# PLCArduinoV1.net
KiCad netlist of a schematic drawn in EAGLE
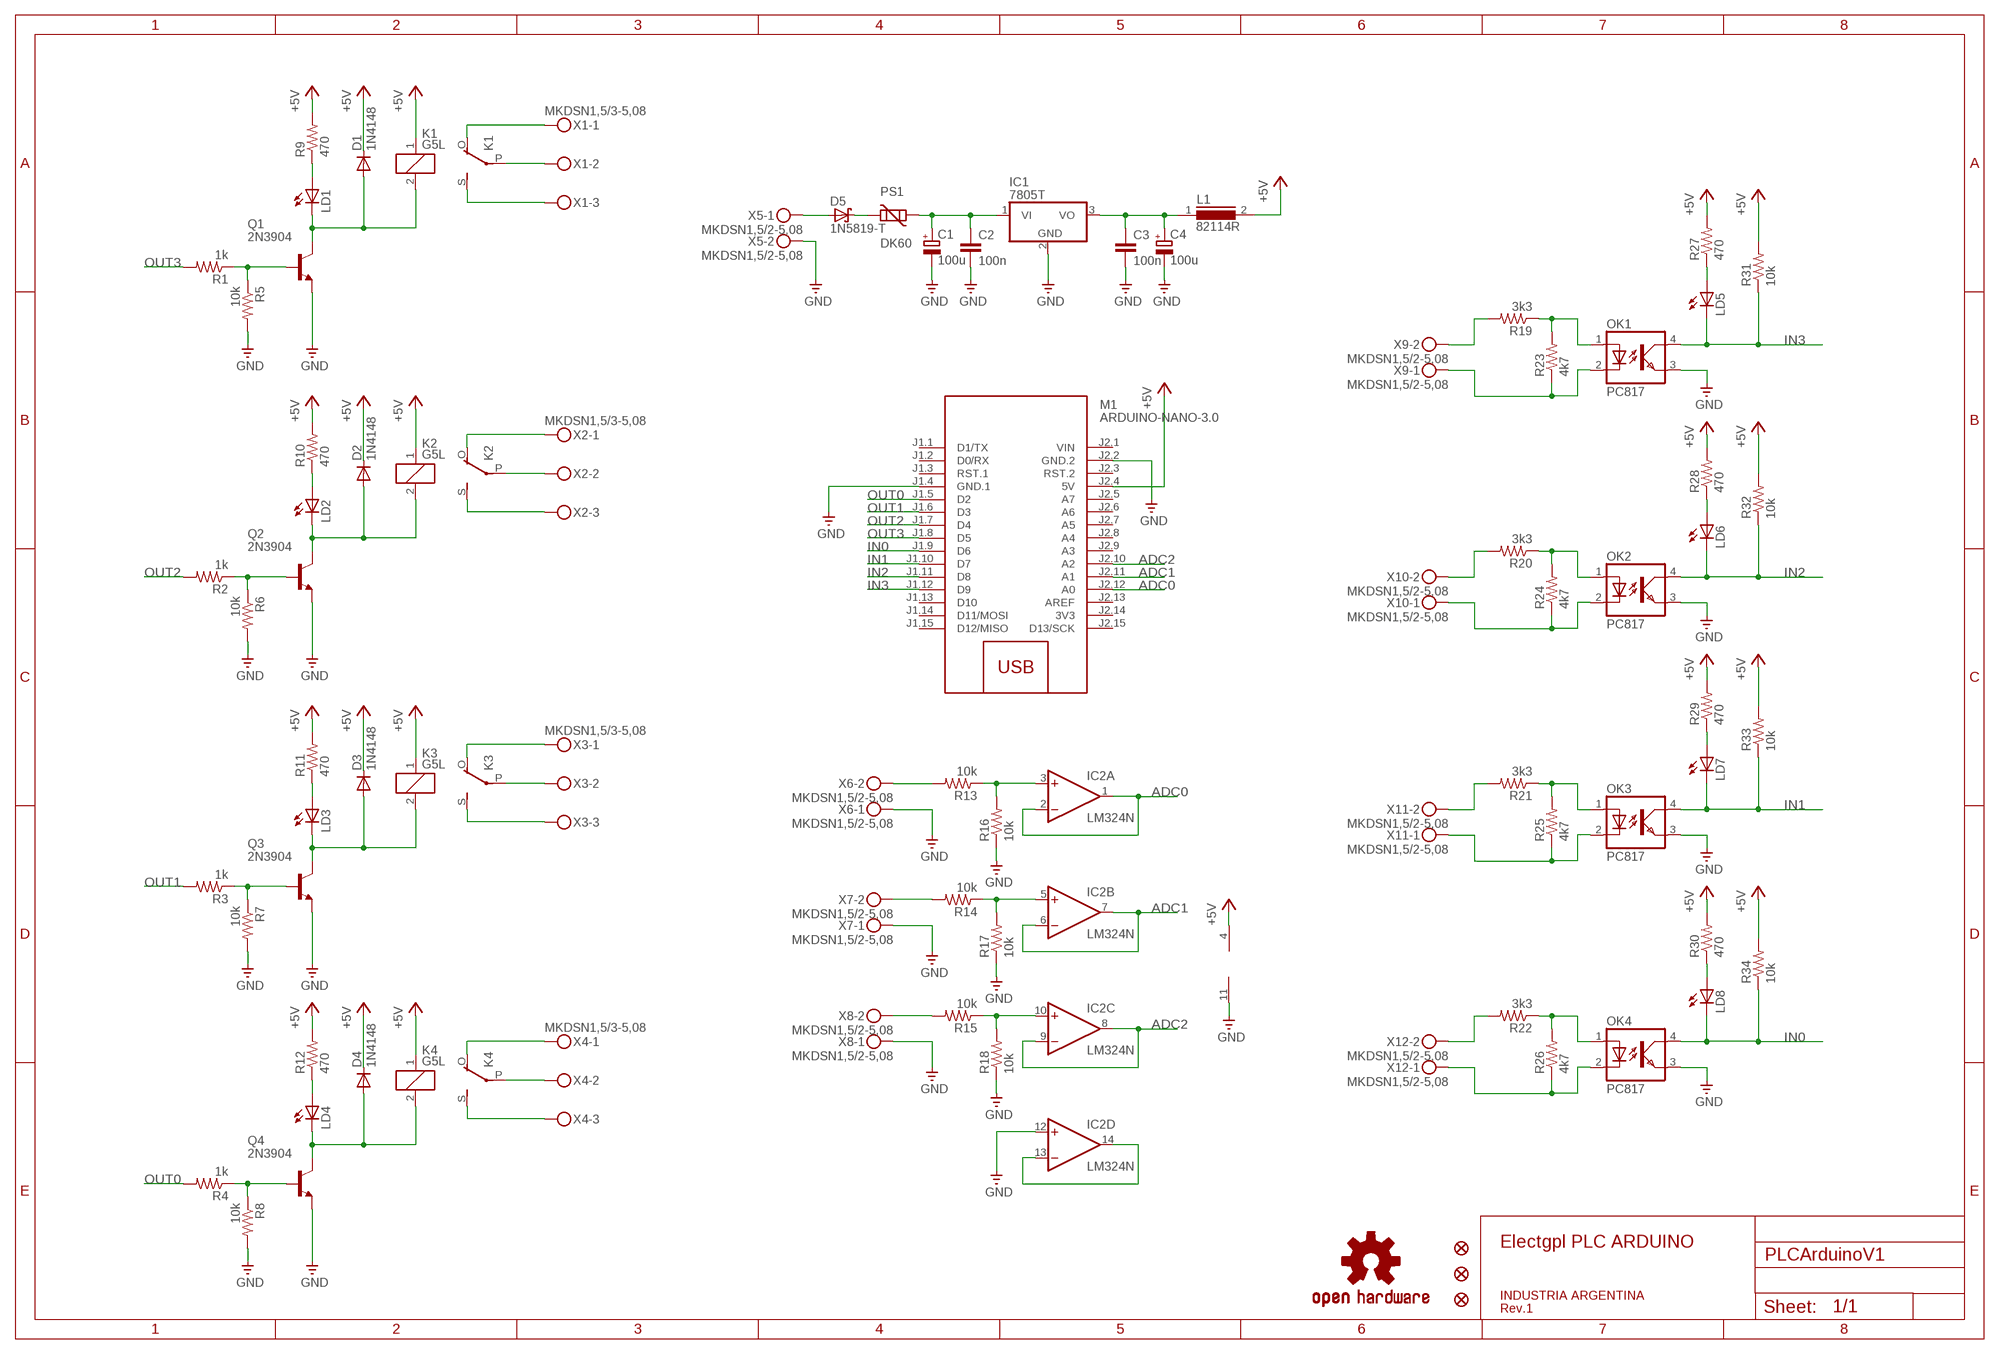
[diagram p0: schematic, sheet 1]

(export (version "E")
  (design (tool "Eeschema 10.0.6"))
  (components
    (comp (ref "C1")
      (value "100u")
      (footprint "eagle-import:E3,5-8")
      (libsource (lib "eagle-import") (part "CPOL-EUE3.5-8"))
    )
    (comp (ref "C2")
      (value "100n")
      (footprint "eagle-import:C050-024X044")
      (libsource (lib "eagle-import") (part "C-EU050-024X044"))
    )
    (comp (ref "C3")
      (value "100n")
      (footprint "eagle-import:C050-024X044")
      (libsource (lib "eagle-import") (part "C-EU050-024X044"))
    )
    (comp (ref "C4")
      (value "100u")
      (footprint "eagle-import:E3,5-8")
      (libsource (lib "eagle-import") (part "CPOL-EUE3.5-8"))
    )
    (comp (ref "D1")
      (value "1N4148")
      (footprint "eagle-import:DO35-10")
      (libsource (lib "eagle-import") (part "1N4148"))
    )
    (comp (ref "D2")
      (value "1N4148")
      (footprint "eagle-import:DO35-10")
      (libsource (lib "eagle-import") (part "1N4148"))
    )
    (comp (ref "D3")
      (value "1N4148")
      (footprint "eagle-import:DO35-10")
      (libsource (lib "eagle-import") (part "1N4148"))
    )
    (comp (ref "D4")
      (value "1N4148")
      (footprint "eagle-import:DO35-10")
      (libsource (lib "eagle-import") (part "1N4148"))
    )
    (comp (ref "D5")
      (value "1N5819-T")
      (footprint "eagle-import:DO41-7.6")
      (libsource (lib "eagle-import") (part "1N5819-T"))
    )
    (comp (ref "IC1")
      (value "7805T")
      (footprint "eagle-import:TO220H")
      (libsource (lib "eagle-import") (part "78T05"))
    )
    (comp (ref "IC2")
      (value "LM324N")
      (footprint "eagle-import:DIL14")
      (libsource (lib "eagle-import") (part "LM324N"))
    )
    (comp (ref "JP1")
      (value "FIDUCIAL1X2.5")
      (footprint "eagle-import:FIDUCIAL-1X2.5")
      (libsource (lib "eagle-import") (part "FIDUCIAL1X2.5"))
    )
    (comp (ref "JP2")
      (value "FIDUCIAL1X2.5")
      (footprint "eagle-import:FIDUCIAL-1X2.5")
      (libsource (lib "eagle-import") (part "FIDUCIAL1X2.5"))
    )
    (comp (ref "JP3")
      (value "FIDUCIAL1X2.5")
      (footprint "eagle-import:FIDUCIAL-1X2.5")
      (libsource (lib "eagle-import") (part "FIDUCIAL1X2.5"))
    )
    (comp (ref "K1")
      (value "G5L")
      (footprint "eagle-import:G5LE")
      (libsource (lib "eagle-import") (part "G5L"))
    )
    (comp (ref "K2")
      (value "G5L")
      (footprint "eagle-import:G5LE")
      (libsource (lib "eagle-import") (part "G5L"))
    )
    (comp (ref "K3")
      (value "G5L")
      (footprint "eagle-import:G5LE")
      (libsource (lib "eagle-import") (part "G5L"))
    )
    (comp (ref "K4")
      (value "G5L")
      (footprint "eagle-import:G5LE")
      (libsource (lib "eagle-import") (part "G5L"))
    )
    (comp (ref "L1")
      (value "82114R")
      (footprint "eagle-import:82114R")
      (libsource (lib "eagle-import") (part "82114R"))
    )
    (comp (ref "LD1")
      (value "LED3MM")
      (footprint "eagle-import:LED3MM")
      (libsource (lib "eagle-import") (part "LED3MM"))
    )
    (comp (ref "LD2")
      (value "LED3MM")
      (footprint "eagle-import:LED3MM")
      (libsource (lib "eagle-import") (part "LED3MM"))
    )
    (comp (ref "LD3")
      (value "LED3MM")
      (footprint "eagle-import:LED3MM")
      (libsource (lib "eagle-import") (part "LED3MM"))
    )
    (comp (ref "LD4")
      (value "LED3MM")
      (footprint "eagle-import:LED3MM")
      (libsource (lib "eagle-import") (part "LED3MM"))
    )
    (comp (ref "LD5")
      (value "LED3MM")
      (footprint "eagle-import:LED3MM")
      (libsource (lib "eagle-import") (part "LED3MM"))
    )
    (comp (ref "LD6")
      (value "LED3MM")
      (footprint "eagle-import:LED3MM")
      (libsource (lib "eagle-import") (part "LED3MM"))
    )
    (comp (ref "LD7")
      (value "LED3MM")
      (footprint "eagle-import:LED3MM")
      (libsource (lib "eagle-import") (part "LED3MM"))
    )
    (comp (ref "LD8")
      (value "LED3MM")
      (footprint "eagle-import:LED3MM")
      (libsource (lib "eagle-import") (part "LED3MM"))
    )
    (comp (ref "M1")
      (value "ARDUINO-NANO-3.0")
      (footprint "eagle-import:ARDUINO-NANO-3.0")
      (libsource (lib "eagle-import") (part "ARDUINO-NANO-3.0"))
    )
    (comp (ref "OK1")
      (value "PC817")
      (footprint "eagle-import:DIL04")
      (libsource (lib "eagle-import") (part "PC817"))
    )
    (comp (ref "OK2")
      (value "PC817")
      (footprint "eagle-import:DIL04")
      (libsource (lib "eagle-import") (part "PC817"))
    )
    (comp (ref "OK3")
      (value "PC817")
      (footprint "eagle-import:DIL04")
      (libsource (lib "eagle-import") (part "PC817"))
    )
    (comp (ref "OK4")
      (value "PC817")
      (footprint "eagle-import:DIL04")
      (libsource (lib "eagle-import") (part "PC817"))
    )
    (comp (ref "PS1")
      (value "DK60")
      (footprint "eagle-import:SO5K11")
      (libsource (lib "eagle-import") (part "POLYSWITCH5MM"))
    )
    (comp (ref "Q1")
      (value "2N3904")
      (footprint "eagle-import:TO92")
      (libsource (lib "eagle-import") (part "2N3904"))
    )
    (comp (ref "Q2")
      (value "2N3904")
      (footprint "eagle-import:TO92")
      (libsource (lib "eagle-import") (part "2N3904"))
    )
    (comp (ref "Q3")
      (value "2N3904")
      (footprint "eagle-import:TO92")
      (libsource (lib "eagle-import") (part "2N3904"))
    )
    (comp (ref "Q4")
      (value "2N3904")
      (footprint "eagle-import:TO92")
      (libsource (lib "eagle-import") (part "2N3904"))
    )
    (comp (ref "R1")
      (value "1k")
      (footprint "eagle-import:0204_5")
      (libsource (lib "eagle-import") (part "R-US_0204/5"))
    )
    (comp (ref "R2")
      (value "1k")
      (footprint "eagle-import:0204_5")
      (libsource (lib "eagle-import") (part "R-US_0204/5"))
    )
    (comp (ref "R3")
      (value "1k")
      (footprint "eagle-import:0204_5")
      (libsource (lib "eagle-import") (part "R-US_0204/5"))
    )
    (comp (ref "R4")
      (value "1k")
      (footprint "eagle-import:0204_5")
      (libsource (lib "eagle-import") (part "R-US_0204/5"))
    )
    (comp (ref "R5")
      (value "10k")
      (footprint "eagle-import:0204_5")
      (libsource (lib "eagle-import") (part "R-US_0204/5"))
    )
    (comp (ref "R6")
      (value "10k")
      (footprint "eagle-import:0204_5")
      (libsource (lib "eagle-import") (part "R-US_0204/5"))
    )
    (comp (ref "R7")
      (value "10k")
      (footprint "eagle-import:0204_5")
      (libsource (lib "eagle-import") (part "R-US_0204/5"))
    )
    (comp (ref "R8")
      (value "10k")
      (footprint "eagle-import:0204_5")
      (libsource (lib "eagle-import") (part "R-US_0204/5"))
    )
    (comp (ref "R9")
      (value "470")
      (footprint "eagle-import:0204_5")
      (libsource (lib "eagle-import") (part "R-US_0204/5"))
    )
    (comp (ref "R10")
      (value "470")
      (footprint "eagle-import:0204_5")
      (libsource (lib "eagle-import") (part "R-US_0204/5"))
    )
    (comp (ref "R11")
      (value "470")
      (footprint "eagle-import:0204_5")
      (libsource (lib "eagle-import") (part "R-US_0204/5"))
    )
    (comp (ref "R12")
      (value "470")
      (footprint "eagle-import:0204_5")
      (libsource (lib "eagle-import") (part "R-US_0204/5"))
    )
    (comp (ref "R13")
      (value "10k")
      (footprint "eagle-import:0204_5")
      (libsource (lib "eagle-import") (part "R-US_0204/5"))
    )
    (comp (ref "R14")
      (value "10k")
      (footprint "eagle-import:0204_5")
      (libsource (lib "eagle-import") (part "R-US_0204/5"))
    )
    (comp (ref "R15")
      (value "10k")
      (footprint "eagle-import:0204_5")
      (libsource (lib "eagle-import") (part "R-US_0204/5"))
    )
    (comp (ref "R16")
      (value "10k")
      (footprint "eagle-import:0204_5")
      (libsource (lib "eagle-import") (part "R-US_0204/5"))
    )
    (comp (ref "R17")
      (value "10k")
      (footprint "eagle-import:0204_5")
      (libsource (lib "eagle-import") (part "R-US_0204/5"))
    )
    (comp (ref "R18")
      (value "10k")
      (footprint "eagle-import:0204_5")
      (libsource (lib "eagle-import") (part "R-US_0204/5"))
    )
    (comp (ref "R19")
      (value "3k3")
      (footprint "eagle-import:0204_5")
      (libsource (lib "eagle-import") (part "R-US_0204/5"))
    )
    (comp (ref "R20")
      (value "3k3")
      (footprint "eagle-import:0204_5")
      (libsource (lib "eagle-import") (part "R-US_0204/5"))
    )
    (comp (ref "R21")
      (value "3k3")
      (footprint "eagle-import:0204_5")
      (libsource (lib "eagle-import") (part "R-US_0204/5"))
    )
    (comp (ref "R22")
      (value "3k3")
      (footprint "eagle-import:0204_5")
      (libsource (lib "eagle-import") (part "R-US_0204/5"))
    )
    (comp (ref "R23")
      (value "4k7")
      (footprint "eagle-import:0204_5")
      (libsource (lib "eagle-import") (part "R-US_0204/5"))
    )
    (comp (ref "R24")
      (value "4k7")
      (footprint "eagle-import:0204_5")
      (libsource (lib "eagle-import") (part "R-US_0204/5"))
    )
    (comp (ref "R25")
      (value "4k7")
      (footprint "eagle-import:0204_5")
      (libsource (lib "eagle-import") (part "R-US_0204/5"))
    )
    (comp (ref "R26")
      (value "4k7")
      (footprint "eagle-import:0204_5")
      (libsource (lib "eagle-import") (part "R-US_0204/5"))
    )
    (comp (ref "R27")
      (value "470")
      (footprint "eagle-import:0204_5")
      (libsource (lib "eagle-import") (part "R-US_0204/5"))
    )
    (comp (ref "R28")
      (value "470")
      (footprint "eagle-import:0204_5")
      (libsource (lib "eagle-import") (part "R-US_0204/5"))
    )
    (comp (ref "R29")
      (value "470")
      (footprint "eagle-import:0204_5")
      (libsource (lib "eagle-import") (part "R-US_0204/5"))
    )
    (comp (ref "R30")
      (value "470")
      (footprint "eagle-import:0204_5")
      (libsource (lib "eagle-import") (part "R-US_0204/5"))
    )
    (comp (ref "R31")
      (value "10k")
      (footprint "eagle-import:0204_5")
      (libsource (lib "eagle-import") (part "R-US_0204/5"))
    )
    (comp (ref "R32")
      (value "10k")
      (footprint "eagle-import:0204_5")
      (libsource (lib "eagle-import") (part "R-US_0204/5"))
    )
    (comp (ref "R33")
      (value "10k")
      (footprint "eagle-import:0204_5")
      (libsource (lib "eagle-import") (part "R-US_0204/5"))
    )
    (comp (ref "R34")
      (value "10k")
      (footprint "eagle-import:0204_5")
      (libsource (lib "eagle-import") (part "R-US_0204/5"))
    )
    (comp (ref "U1")
      (value "OSHW-LOGOM")
      (footprint "eagle-import:OSHW-LOGO-M")
      (libsource (lib "eagle-import") (part "OSHW-LOGOM"))
    )
    (comp (ref "X1")
      (value "MKDSN1,5/3-5,08")
      (footprint "eagle-import:MKDSN1,5_3-5,08")
      (libsource (lib "eagle-import") (part "MKDSN1,5/3-5,08"))
    )
    (comp (ref "X2")
      (value "MKDSN1,5/3-5,08")
      (footprint "eagle-import:MKDSN1,5_3-5,08")
      (libsource (lib "eagle-import") (part "MKDSN1,5/3-5,08"))
    )
    (comp (ref "X3")
      (value "MKDSN1,5/3-5,08")
      (footprint "eagle-import:MKDSN1,5_3-5,08")
      (libsource (lib "eagle-import") (part "MKDSN1,5/3-5,08"))
    )
    (comp (ref "X4")
      (value "MKDSN1,5/3-5,08")
      (footprint "eagle-import:MKDSN1,5_3-5,08")
      (libsource (lib "eagle-import") (part "MKDSN1,5/3-5,08"))
    )
    (comp (ref "X5")
      (value "MKDSN1,5/2-5,08")
      (footprint "eagle-import:MKDSN1,5_2-5,08")
      (libsource (lib "eagle-import") (part "MKDSN1,5/2-5,08"))
    )
    (comp (ref "X6")
      (value "MKDSN1,5/2-5,08")
      (footprint "eagle-import:MKDSN1,5_2-5,08")
      (libsource (lib "eagle-import") (part "MKDSN1,5/2-5,08"))
    )
    (comp (ref "X7")
      (value "MKDSN1,5/2-5,08")
      (footprint "eagle-import:MKDSN1,5_2-5,08")
      (libsource (lib "eagle-import") (part "MKDSN1,5/2-5,08"))
    )
    (comp (ref "X8")
      (value "MKDSN1,5/2-5,08")
      (footprint "eagle-import:MKDSN1,5_2-5,08")
      (libsource (lib "eagle-import") (part "MKDSN1,5/2-5,08"))
    )
    (comp (ref "X9")
      (value "MKDSN1,5/2-5,08")
      (footprint "eagle-import:MKDSN1,5_2-5,08")
      (libsource (lib "eagle-import") (part "MKDSN1,5/2-5,08"))
    )
    (comp (ref "X10")
      (value "MKDSN1,5/2-5,08")
      (footprint "eagle-import:MKDSN1,5_2-5,08")
      (libsource (lib "eagle-import") (part "MKDSN1,5/2-5,08"))
    )
    (comp (ref "X11")
      (value "MKDSN1,5/2-5,08")
      (footprint "eagle-import:MKDSN1,5_2-5,08")
      (libsource (lib "eagle-import") (part "MKDSN1,5/2-5,08"))
    )
    (comp (ref "X12")
      (value "MKDSN1,5/2-5,08")
      (footprint "eagle-import:MKDSN1,5_2-5,08")
      (libsource (lib "eagle-import") (part "MKDSN1,5/2-5,08"))
    )
  )
  (nets
    (net (code "1") (name "+5V") (class "Default")
      (node (ref "D1") (pin "C") (pinfunction "C_C") (pintype "passive"))
      (node (ref "D2") (pin "C") (pinfunction "C_C") (pintype "passive"))
      (node (ref "D3") (pin "C") (pinfunction "C_C") (pintype "passive"))
      (node (ref "D4") (pin "C") (pinfunction "C_C") (pintype "passive"))
      (node (ref "IC2") (pin "4") (pinfunction "V+_4") (pintype "power_in"))
      (node (ref "K1") (pin "1") (pinfunction "1_1") (pintype "passive"))
      (node (ref "K2") (pin "1") (pinfunction "1_1") (pintype "passive"))
      (node (ref "K3") (pin "1") (pinfunction "1_1") (pintype "passive"))
      (node (ref "K4") (pin "1") (pinfunction "1_1") (pintype "passive"))
      (node (ref "L1") (pin "2") (pinfunction "2_2") (pintype "passive"))
      (node (ref "M1") (pin "J2.4") (pinfunction "5V_J2.4") (pintype "power_in"))
      (node (ref "R10") (pin "2") (pinfunction "2_2") (pintype "passive"))
      (node (ref "R11") (pin "2") (pinfunction "2_2") (pintype "passive"))
      (node (ref "R12") (pin "2") (pinfunction "2_2") (pintype "passive"))
      (node (ref "R27") (pin "2") (pinfunction "2_2") (pintype "passive"))
      (node (ref "R28") (pin "2") (pinfunction "2_2") (pintype "passive"))
      (node (ref "R29") (pin "2") (pinfunction "2_2") (pintype "passive"))
      (node (ref "R30") (pin "2") (pinfunction "2_2") (pintype "passive"))
      (node (ref "R31") (pin "2") (pinfunction "2_2") (pintype "passive"))
      (node (ref "R32") (pin "2") (pinfunction "2_2") (pintype "passive"))
      (node (ref "R33") (pin "2") (pinfunction "2_2") (pintype "passive"))
      (node (ref "R34") (pin "2") (pinfunction "2_2") (pintype "passive"))
      (node (ref "R9") (pin "2") (pinfunction "2_2") (pintype "passive"))
    )
    (net (code "2") (name "/3V3") (class "Default")
      (node (ref "M1") (pin "J2.14") (pinfunction "3V3_J2.14") (pintype "power_in"))
    )
    (net (code "3") (name "/ADC0") (class "Default")
      (node (ref "IC2") (pin "1") (pinfunction "OUT_1") (pintype "output"))
      (node (ref "IC2") (pin "2") (pinfunction "-IN_2") (pintype "input"))
      (node (ref "M1") (pin "J2.12") (pinfunction "A0_J2.12") (pintype "bidirectional"))
    )
    (net (code "4") (name "/ADC1") (class "Default")
      (node (ref "IC2") (pin "6") (pinfunction "-IN_6") (pintype "input"))
      (node (ref "IC2") (pin "7") (pinfunction "OUT_7") (pintype "output"))
      (node (ref "M1") (pin "J2.11") (pinfunction "A1_J2.11") (pintype "bidirectional"))
    )
    (net (code "5") (name "/ADC2") (class "Default")
      (node (ref "IC2") (pin "8") (pinfunction "OUT_8") (pintype "output"))
      (node (ref "IC2") (pin "9") (pinfunction "-IN_9") (pintype "input"))
      (node (ref "M1") (pin "J2.10") (pinfunction "A2_J2.10") (pintype "bidirectional"))
    )
    (net (code "6") (name "/IN0") (class "Default")
      (node (ref "LD8") (pin "K") (pinfunction "C_K") (pintype "passive"))
      (node (ref "M1") (pin "J1.9") (pinfunction "D6_J1.9") (pintype "bidirectional"))
      (node (ref "OK4") (pin "4") (pinfunction "COL_4") (pintype "passive"))
      (node (ref "R34") (pin "1") (pinfunction "1_1") (pintype "passive"))
    )
    (net (code "7") (name "/IN1") (class "Default")
      (node (ref "LD7") (pin "K") (pinfunction "C_K") (pintype "passive"))
      (node (ref "M1") (pin "J1.10") (pinfunction "D7_J1.10") (pintype "bidirectional"))
      (node (ref "OK3") (pin "4") (pinfunction "COL_4") (pintype "passive"))
      (node (ref "R33") (pin "1") (pinfunction "1_1") (pintype "passive"))
    )
    (net (code "8") (name "/IN2") (class "Default")
      (node (ref "LD6") (pin "K") (pinfunction "C_K") (pintype "passive"))
      (node (ref "M1") (pin "J1.11") (pinfunction "D8_J1.11") (pintype "bidirectional"))
      (node (ref "OK2") (pin "4") (pinfunction "COL_4") (pintype "passive"))
      (node (ref "R32") (pin "1") (pinfunction "1_1") (pintype "passive"))
    )
    (net (code "9") (name "/IN3") (class "Default")
      (node (ref "LD5") (pin "K") (pinfunction "C_K") (pintype "passive"))
      (node (ref "M1") (pin "J1.12") (pinfunction "D9_J1.12") (pintype "bidirectional"))
      (node (ref "OK1") (pin "4") (pinfunction "COL_4") (pintype "passive"))
      (node (ref "R31") (pin "1") (pinfunction "1_1") (pintype "passive"))
    )
    (net (code "10") (name "/OUT0") (class "Default")
      (node (ref "M1") (pin "J1.5") (pinfunction "D2_J1.5") (pintype "bidirectional"))
      (node (ref "R4") (pin "2") (pinfunction "2_2") (pintype "passive"))
    )
    (net (code "11") (name "/OUT1") (class "Default")
      (node (ref "M1") (pin "J1.6") (pinfunction "D3_J1.6") (pintype "bidirectional"))
      (node (ref "R3") (pin "2") (pinfunction "2_2") (pintype "passive"))
    )
    (net (code "12") (name "/OUT2") (class "Default")
      (node (ref "M1") (pin "J1.7") (pinfunction "D4_J1.7") (pintype "bidirectional"))
      (node (ref "R2") (pin "2") (pinfunction "2_2") (pintype "passive"))
    )
    (net (code "13") (name "/OUT3") (class "Default")
      (node (ref "M1") (pin "J1.8") (pinfunction "D5_J1.8") (pintype "bidirectional"))
      (node (ref "R1") (pin "2") (pinfunction "2_2") (pintype "passive"))
    )
    (net (code "14") (name "/VIN") (class "Default")
      (node (ref "M1") (pin "J2.1") (pinfunction "VIN_J2.1") (pintype "power_in"))
    )
    (net (code "15") (name "GND") (class "Default")
      (node (ref "C1") (pin "-") (pinfunction "-_-") (pintype "passive"))
      (node (ref "C2") (pin "2") (pinfunction "2_2") (pintype "passive"))
      (node (ref "C3") (pin "2") (pinfunction "2_2") (pintype "passive"))
      (node (ref "C4") (pin "-") (pinfunction "-_-") (pintype "passive"))
      (node (ref "IC1") (pin "2") (pinfunction "GND_2") (pintype "passive"))
      (node (ref "IC2") (pin "11") (pinfunction "V-_11") (pintype "power_in"))
      (node (ref "IC2") (pin "12") (pinfunction "+IN_12") (pintype "input"))
      (node (ref "M1") (pin "J1.4") (pinfunction "GND.1_J1.4") (pintype "power_in"))
      (node (ref "M1") (pin "J2.2") (pinfunction "GND.2_J2.2") (pintype "power_in"))
      (node (ref "OK1") (pin "3") (pinfunction "EMIT_3") (pintype "passive"))
      (node (ref "OK2") (pin "3") (pinfunction "EMIT_3") (pintype "passive"))
      (node (ref "OK3") (pin "3") (pinfunction "EMIT_3") (pintype "passive"))
      (node (ref "OK4") (pin "3") (pinfunction "EMIT_3") (pintype "passive"))
      (node (ref "Q1") (pin "3") (pinfunction "E_3") (pintype "passive"))
      (node (ref "Q2") (pin "3") (pinfunction "E_3") (pintype "passive"))
      (node (ref "Q3") (pin "3") (pinfunction "E_3") (pintype "passive"))
      (node (ref "Q4") (pin "3") (pinfunction "E_3") (pintype "passive"))
      (node (ref "R16") (pin "1") (pinfunction "1_1") (pintype "passive"))
      (node (ref "R17") (pin "1") (pinfunction "1_1") (pintype "passive"))
      (node (ref "R18") (pin "1") (pinfunction "1_1") (pintype "passive"))
      (node (ref "R5") (pin "2") (pinfunction "2_2") (pintype "passive"))
      (node (ref "R6") (pin "2") (pinfunction "2_2") (pintype "passive"))
      (node (ref "R7") (pin "2") (pinfunction "2_2") (pintype "passive"))
      (node (ref "R8") (pin "2") (pinfunction "2_2") (pintype "passive"))
      (node (ref "X5") (pin "2") (pinfunction "KL_2") (pintype "passive"))
      (node (ref "X6") (pin "1") (pinfunction "KL_1") (pintype "passive"))
      (node (ref "X7") (pin "1") (pinfunction "KL_1") (pintype "passive"))
      (node (ref "X8") (pin "1") (pinfunction "KL_1") (pintype "passive"))
    )
    (net (code "16") (name "Net-(D5-PadC)") (class "Default")
      (node (ref "D5") (pin "C") (pinfunction "C_C") (pintype "passive"))
      (node (ref "PS1") (pin "2") (pinfunction "2_2") (pintype "passive"))
    )
    (net (code "17") (name "Net-(IC1-VI)") (class "Default")
      (node (ref "C1") (pin "+") (pinfunction "+_+") (pintype "passive"))
      (node (ref "C2") (pin "1") (pinfunction "1_1") (pintype "passive"))
      (node (ref "IC1") (pin "1") (pinfunction "VI_1") (pintype "input"))
      (node (ref "PS1") (pin "1") (pinfunction "1_1") (pintype "passive"))
    )
    (net (code "18") (name "Net-(IC1-VO)") (class "Default")
      (node (ref "C3") (pin "1") (pinfunction "1_1") (pintype "passive"))
      (node (ref "C4") (pin "+") (pinfunction "+_+") (pintype "passive"))
      (node (ref "IC1") (pin "3") (pinfunction "VO_3") (pintype "passive"))
      (node (ref "L1") (pin "1") (pinfunction "1_1") (pintype "passive"))
    )
    (net (code "19") (name "Net-(IC2A-+IN)") (class "Default")
      (node (ref "IC2") (pin "3") (pinfunction "+IN_3") (pintype "input"))
      (node (ref "R13") (pin "1") (pinfunction "1_1") (pintype "passive"))
      (node (ref "R16") (pin "2") (pinfunction "2_2") (pintype "passive"))
    )
    (net (code "20") (name "Net-(IC2B-+IN)") (class "Default")
      (node (ref "IC2") (pin "5") (pinfunction "+IN_5") (pintype "input"))
      (node (ref "R14") (pin "1") (pinfunction "1_1") (pintype "passive"))
      (node (ref "R17") (pin "2") (pinfunction "2_2") (pintype "passive"))
    )
    (net (code "21") (name "Net-(IC2C-+IN)") (class "Default")
      (node (ref "IC2") (pin "10") (pinfunction "+IN_10") (pintype "input"))
      (node (ref "R15") (pin "1") (pinfunction "1_1") (pintype "passive"))
      (node (ref "R18") (pin "2") (pinfunction "2_2") (pintype "passive"))
    )
    (net (code "22") (name "Net-(IC2D--IN)") (class "Default")
      (node (ref "IC2") (pin "13") (pinfunction "-IN_13") (pintype "input"))
      (node (ref "IC2") (pin "14") (pinfunction "OUT_14") (pintype "output"))
    )
    (net (code "23") (name "Net-(LD1-C)") (class "Default")
      (node (ref "D1") (pin "A") (pinfunction "A_A") (pintype "passive"))
      (node (ref "K1") (pin "2") (pinfunction "2_2") (pintype "passive"))
      (node (ref "LD1") (pin "K") (pinfunction "C_K") (pintype "passive"))
      (node (ref "Q1") (pin "1") (pinfunction "C_1") (pintype "passive"))
    )
    (net (code "24") (name "Net-(LD1-PadA)") (class "Default")
      (node (ref "LD1") (pin "A") (pinfunction "A_A") (pintype "passive"))
      (node (ref "R9") (pin "1") (pinfunction "1_1") (pintype "passive"))
    )
    (net (code "25") (name "Net-(LD2-C)") (class "Default")
      (node (ref "D2") (pin "A") (pinfunction "A_A") (pintype "passive"))
      (node (ref "K2") (pin "2") (pinfunction "2_2") (pintype "passive"))
      (node (ref "LD2") (pin "K") (pinfunction "C_K") (pintype "passive"))
      (node (ref "Q2") (pin "1") (pinfunction "C_1") (pintype "passive"))
    )
    (net (code "26") (name "Net-(LD2-PadA)") (class "Default")
      (node (ref "LD2") (pin "A") (pinfunction "A_A") (pintype "passive"))
      (node (ref "R10") (pin "1") (pinfunction "1_1") (pintype "passive"))
    )
    (net (code "27") (name "Net-(LD3-C)") (class "Default")
      (node (ref "D3") (pin "A") (pinfunction "A_A") (pintype "passive"))
      (node (ref "K3") (pin "2") (pinfunction "2_2") (pintype "passive"))
      (node (ref "LD3") (pin "K") (pinfunction "C_K") (pintype "passive"))
      (node (ref "Q3") (pin "1") (pinfunction "C_1") (pintype "passive"))
    )
    (net (code "28") (name "Net-(LD3-PadA)") (class "Default")
      (node (ref "LD3") (pin "A") (pinfunction "A_A") (pintype "passive"))
      (node (ref "R11") (pin "1") (pinfunction "1_1") (pintype "passive"))
    )
    (net (code "29") (name "Net-(LD4-C)") (class "Default")
      (node (ref "D4") (pin "A") (pinfunction "A_A") (pintype "passive"))
      (node (ref "K4") (pin "2") (pinfunction "2_2") (pintype "passive"))
      (node (ref "LD4") (pin "K") (pinfunction "C_K") (pintype "passive"))
      (node (ref "Q4") (pin "1") (pinfunction "C_1") (pintype "passive"))
    )
    (net (code "30") (name "Net-(LD4-PadA)") (class "Default")
      (node (ref "LD4") (pin "A") (pinfunction "A_A") (pintype "passive"))
      (node (ref "R12") (pin "1") (pinfunction "1_1") (pintype "passive"))
    )
    (net (code "31") (name "Net-(LD5-PadA)") (class "Default")
      (node (ref "LD5") (pin "A") (pinfunction "A_A") (pintype "passive"))
      (node (ref "R27") (pin "1") (pinfunction "1_1") (pintype "passive"))
    )
    (net (code "32") (name "Net-(LD6-PadA)") (class "Default")
      (node (ref "LD6") (pin "A") (pinfunction "A_A") (pintype "passive"))
      (node (ref "R28") (pin "1") (pinfunction "1_1") (pintype "passive"))
    )
    (net (code "33") (name "Net-(LD7-PadA)") (class "Default")
      (node (ref "LD7") (pin "A") (pinfunction "A_A") (pintype "passive"))
      (node (ref "R29") (pin "1") (pinfunction "1_1") (pintype "passive"))
    )
    (net (code "34") (name "Net-(LD8-PadA)") (class "Default")
      (node (ref "LD8") (pin "A") (pinfunction "A_A") (pintype "passive"))
      (node (ref "R30") (pin "1") (pinfunction "1_1") (pintype "passive"))
    )
    (net (code "35") (name "Net-(OK1-A)") (class "Default")
      (node (ref "OK1") (pin "1") (pinfunction "A_1") (pintype "passive"))
      (node (ref "R19") (pin "1") (pinfunction "1_1") (pintype "passive"))
      (node (ref "R23") (pin "2") (pinfunction "2_2") (pintype "passive"))
    )
    (net (code "36") (name "Net-(OK1-C)") (class "Default")
      (node (ref "OK1") (pin "2") (pinfunction "C_2") (pintype "passive"))
      (node (ref "R23") (pin "1") (pinfunction "1_1") (pintype "passive"))
      (node (ref "X9") (pin "1") (pinfunction "KL_1") (pintype "passive"))
    )
    (net (code "37") (name "Net-(OK2-A)") (class "Default")
      (node (ref "OK2") (pin "1") (pinfunction "A_1") (pintype "passive"))
      (node (ref "R20") (pin "1") (pinfunction "1_1") (pintype "passive"))
      (node (ref "R24") (pin "2") (pinfunction "2_2") (pintype "passive"))
    )
    (net (code "38") (name "Net-(OK2-C)") (class "Default")
      (node (ref "OK2") (pin "2") (pinfunction "C_2") (pintype "passive"))
      (node (ref "R24") (pin "1") (pinfunction "1_1") (pintype "passive"))
      (node (ref "X10") (pin "1") (pinfunction "KL_1") (pintype "passive"))
    )
    (net (code "39") (name "Net-(OK3-A)") (class "Default")
      (node (ref "OK3") (pin "1") (pinfunction "A_1") (pintype "passive"))
      (node (ref "R21") (pin "1") (pinfunction "1_1") (pintype "passive"))
      (node (ref "R25") (pin "2") (pinfunction "2_2") (pintype "passive"))
    )
    (net (code "40") (name "Net-(OK3-C)") (class "Default")
      (node (ref "OK3") (pin "2") (pinfunction "C_2") (pintype "passive"))
      (node (ref "R25") (pin "1") (pinfunction "1_1") (pintype "passive"))
      (node (ref "X11") (pin "1") (pinfunction "KL_1") (pintype "passive"))
    )
    (net (code "41") (name "Net-(OK4-A)") (class "Default")
      (node (ref "OK4") (pin "1") (pinfunction "A_1") (pintype "passive"))
      (node (ref "R22") (pin "1") (pinfunction "1_1") (pintype "passive"))
      (node (ref "R26") (pin "2") (pinfunction "2_2") (pintype "passive"))
    )
    (net (code "42") (name "Net-(OK4-C)") (class "Default")
      (node (ref "OK4") (pin "2") (pinfunction "C_2") (pintype "passive"))
      (node (ref "R26") (pin "1") (pinfunction "1_1") (pintype "passive"))
      (node (ref "X12") (pin "1") (pinfunction "KL_1") (pintype "passive"))
    )
    (net (code "43") (name "Net-(Q1-B)") (class "Default")
      (node (ref "Q1") (pin "2") (pinfunction "B_2") (pintype "passive"))
      (node (ref "R1") (pin "1") (pinfunction "1_1") (pintype "passive"))
      (node (ref "R5") (pin "1") (pinfunction "1_1") (pintype "passive"))
    )
    (net (code "44") (name "Net-(Q2-B)") (class "Default")
      (node (ref "Q2") (pin "2") (pinfunction "B_2") (pintype "passive"))
      (node (ref "R2") (pin "1") (pinfunction "1_1") (pintype "passive"))
      (node (ref "R6") (pin "1") (pinfunction "1_1") (pintype "passive"))
    )
    (net (code "45") (name "Net-(Q3-B)") (class "Default")
      (node (ref "Q3") (pin "2") (pinfunction "B_2") (pintype "passive"))
      (node (ref "R3") (pin "1") (pinfunction "1_1") (pintype "passive"))
      (node (ref "R7") (pin "1") (pinfunction "1_1") (pintype "passive"))
    )
    (net (code "46") (name "Net-(Q4-B)") (class "Default")
      (node (ref "Q4") (pin "2") (pinfunction "B_2") (pintype "passive"))
      (node (ref "R4") (pin "1") (pinfunction "1_1") (pintype "passive"))
      (node (ref "R8") (pin "1") (pinfunction "1_1") (pintype "passive"))
    )
    (net (code "47") (name "Net-(X1A-KL)") (class "Default")
      (node (ref "K1") (pin "O") (pinfunction "O_O") (pintype "passive"))
      (node (ref "X1") (pin "1") (pinfunction "KL_1") (pintype "passive"))
    )
    (net (code "48") (name "Net-(X1B-KL)") (class "Default")
      (node (ref "K1") (pin "P") (pinfunction "P_P") (pintype "passive"))
      (node (ref "X1") (pin "2") (pinfunction "KL_2") (pintype "passive"))
    )
    (net (code "49") (name "Net-(X1C-KL)") (class "Default")
      (node (ref "K1") (pin "S") (pinfunction "S_S") (pintype "passive"))
      (node (ref "X1") (pin "3") (pinfunction "KL_3") (pintype "passive"))
    )
    (net (code "50") (name "Net-(X2A-KL)") (class "Default")
      (node (ref "K2") (pin "O") (pinfunction "O_O") (pintype "passive"))
      (node (ref "X2") (pin "1") (pinfunction "KL_1") (pintype "passive"))
    )
    (net (code "51") (name "Net-(X2B-KL)") (class "Default")
      (node (ref "K2") (pin "P") (pinfunction "P_P") (pintype "passive"))
      (node (ref "X2") (pin "2") (pinfunction "KL_2") (pintype "passive"))
    )
    (net (code "52") (name "Net-(X2C-KL)") (class "Default")
      (node (ref "K2") (pin "S") (pinfunction "S_S") (pintype "passive"))
      (node (ref "X2") (pin "3") (pinfunction "KL_3") (pintype "passive"))
    )
    (net (code "53") (name "Net-(X3A-KL)") (class "Default")
      (node (ref "K3") (pin "O") (pinfunction "O_O") (pintype "passive"))
      (node (ref "X3") (pin "1") (pinfunction "KL_1") (pintype "passive"))
    )
    (net (code "54") (name "Net-(X3B-KL)") (class "Default")
      (node (ref "K3") (pin "P") (pinfunction "P_P") (pintype "passive"))
      (node (ref "X3") (pin "2") (pinfunction "KL_2") (pintype "passive"))
    )
    (net (code "55") (name "Net-(X3C-KL)") (class "Default")
      (node (ref "K3") (pin "S") (pinfunction "S_S") (pintype "passive"))
      (node (ref "X3") (pin "3") (pinfunction "KL_3") (pintype "passive"))
    )
    (net (code "56") (name "Net-(X4A-KL)") (class "Default")
      (node (ref "K4") (pin "O") (pinfunction "O_O") (pintype "passive"))
      (node (ref "X4") (pin "1") (pinfunction "KL_1") (pintype "passive"))
    )
    (net (code "57") (name "Net-(X4B-KL)") (class "Default")
      (node (ref "K4") (pin "P") (pinfunction "P_P") (pintype "passive"))
      (node (ref "X4") (pin "2") (pinfunction "KL_2") (pintype "passive"))
    )
    (net (code "58") (name "Net-(X4C-KL)") (class "Default")
      (node (ref "K4") (pin "S") (pinfunction "S_S") (pintype "passive"))
      (node (ref "X4") (pin "3") (pinfunction "KL_3") (pintype "passive"))
    )
    (net (code "59") (name "Net-(X5A-KL)") (class "Default")
      (node (ref "D5") (pin "A") (pinfunction "A_A") (pintype "passive"))
      (node (ref "X5") (pin "1") (pinfunction "KL_1") (pintype "passive"))
    )
    (net (code "60") (name "Net-(X6B-KL)") (class "Default")
      (node (ref "R13") (pin "2") (pinfunction "2_2") (pintype "passive"))
      (node (ref "X6") (pin "2") (pinfunction "KL_2") (pintype "passive"))
    )
    (net (code "61") (name "Net-(X7B-KL)") (class "Default")
      (node (ref "R14") (pin "2") (pinfunction "2_2") (pintype "passive"))
      (node (ref "X7") (pin "2") (pinfunction "KL_2") (pintype "passive"))
    )
    (net (code "62") (name "Net-(X8B-KL)") (class "Default")
      (node (ref "R15") (pin "2") (pinfunction "2_2") (pintype "passive"))
      (node (ref "X8") (pin "2") (pinfunction "KL_2") (pintype "passive"))
    )
    (net (code "63") (name "Net-(X9B-KL)") (class "Default")
      (node (ref "R19") (pin "2") (pinfunction "2_2") (pintype "passive"))
      (node (ref "X9") (pin "2") (pinfunction "KL_2") (pintype "passive"))
    )
    (net (code "64") (name "Net-(X10B-KL)") (class "Default")
      (node (ref "R20") (pin "2") (pinfunction "2_2") (pintype "passive"))
      (node (ref "X10") (pin "2") (pinfunction "KL_2") (pintype "passive"))
    )
    (net (code "65") (name "Net-(X11B-KL)") (class "Default")
      (node (ref "R21") (pin "2") (pinfunction "2_2") (pintype "passive"))
      (node (ref "X11") (pin "2") (pinfunction "KL_2") (pintype "passive"))
    )
    (net (code "66") (name "Net-(X12B-KL)") (class "Default")
      (node (ref "R22") (pin "2") (pinfunction "2_2") (pintype "passive"))
      (node (ref "X12") (pin "2") (pinfunction "KL_2") (pintype "passive"))
    )
    (net (code "67") (name "unconnected-(M1-A3-PadJ2.9)") (class "Default")
      (node (ref "M1") (pin "J2.9") (pinfunction "A3_J2.9") (pintype "bidirectional"))
    )
    (net (code "68") (name "unconnected-(M1-A4-PadJ2.8)") (class "Default")
      (node (ref "M1") (pin "J2.8") (pinfunction "A4_J2.8") (pintype "bidirectional"))
    )
    (net (code "69") (name "unconnected-(M1-A5-PadJ2.7)") (class "Default")
      (node (ref "M1") (pin "J2.7") (pinfunction "A5_J2.7") (pintype "bidirectional"))
    )
    (net (code "70") (name "unconnected-(M1-A6-PadJ2.6)") (class "Default")
      (node (ref "M1") (pin "J2.6") (pinfunction "A6_J2.6") (pintype "bidirectional"))
    )
    (net (code "71") (name "unconnected-(M1-A7-PadJ2.5)") (class "Default")
      (node (ref "M1") (pin "J2.5") (pinfunction "A7_J2.5") (pintype "bidirectional"))
    )
    (net (code "72") (name "unconnected-(M1-AREF-PadJ2.13)") (class "Default")
      (node (ref "M1") (pin "J2.13") (pinfunction "AREF_J2.13") (pintype "bidirectional"))
    )
    (net (code "73") (name "unconnected-(M1-D0{slash}RX-PadJ1.2)") (class "Default")
      (node (ref "M1") (pin "J1.2") (pinfunction "D0/RX_J1.2") (pintype "bidirectional"))
    )
    (net (code "74") (name "unconnected-(M1-D1{slash}TX-PadJ1.1)") (class "Default")
      (node (ref "M1") (pin "J1.1") (pinfunction "D1/TX_J1.1") (pintype "bidirectional"))
    )
    (net (code "75") (name "unconnected-(M1-D10-PadJ1.13)") (class "Default")
      (node (ref "M1") (pin "J1.13") (pinfunction "D10_J1.13") (pintype "bidirectional"))
    )
    (net (code "76") (name "unconnected-(M1-D11{slash}MOSI-PadJ1.14)") (class "Default")
      (node (ref "M1") (pin "J1.14") (pinfunction "D11/MOSI_J1.14") (pintype "bidirectional"))
    )
    (net (code "77") (name "unconnected-(M1-D12{slash}MISO-PadJ1.15)") (class "Default")
      (node (ref "M1") (pin "J1.15") (pinfunction "D12/MISO_J1.15") (pintype "bidirectional"))
    )
    (net (code "78") (name "unconnected-(M1-D13{slash}SCK-PadJ2.15)") (class "Default")
      (node (ref "M1") (pin "J2.15") (pinfunction "D13/SCK_J2.15") (pintype "bidirectional"))
    )
    (net (code "79") (name "unconnected-(M1-RST.1-PadJ1.3)") (class "Default")
      (node (ref "M1") (pin "J1.3") (pinfunction "RST.1_J1.3") (pintype "bidirectional"))
    )
    (net (code "80") (name "unconnected-(M1-RST.2-PadJ2.3)") (class "Default")
      (node (ref "M1") (pin "J2.3") (pinfunction "RST.2_J2.3") (pintype "bidirectional"))
    )
  )
)
